# SCH_WEARBLE_HEALTH_MONITER_2024-07-04.net
KiCad netlist of a schematic drawn in EasyEDA
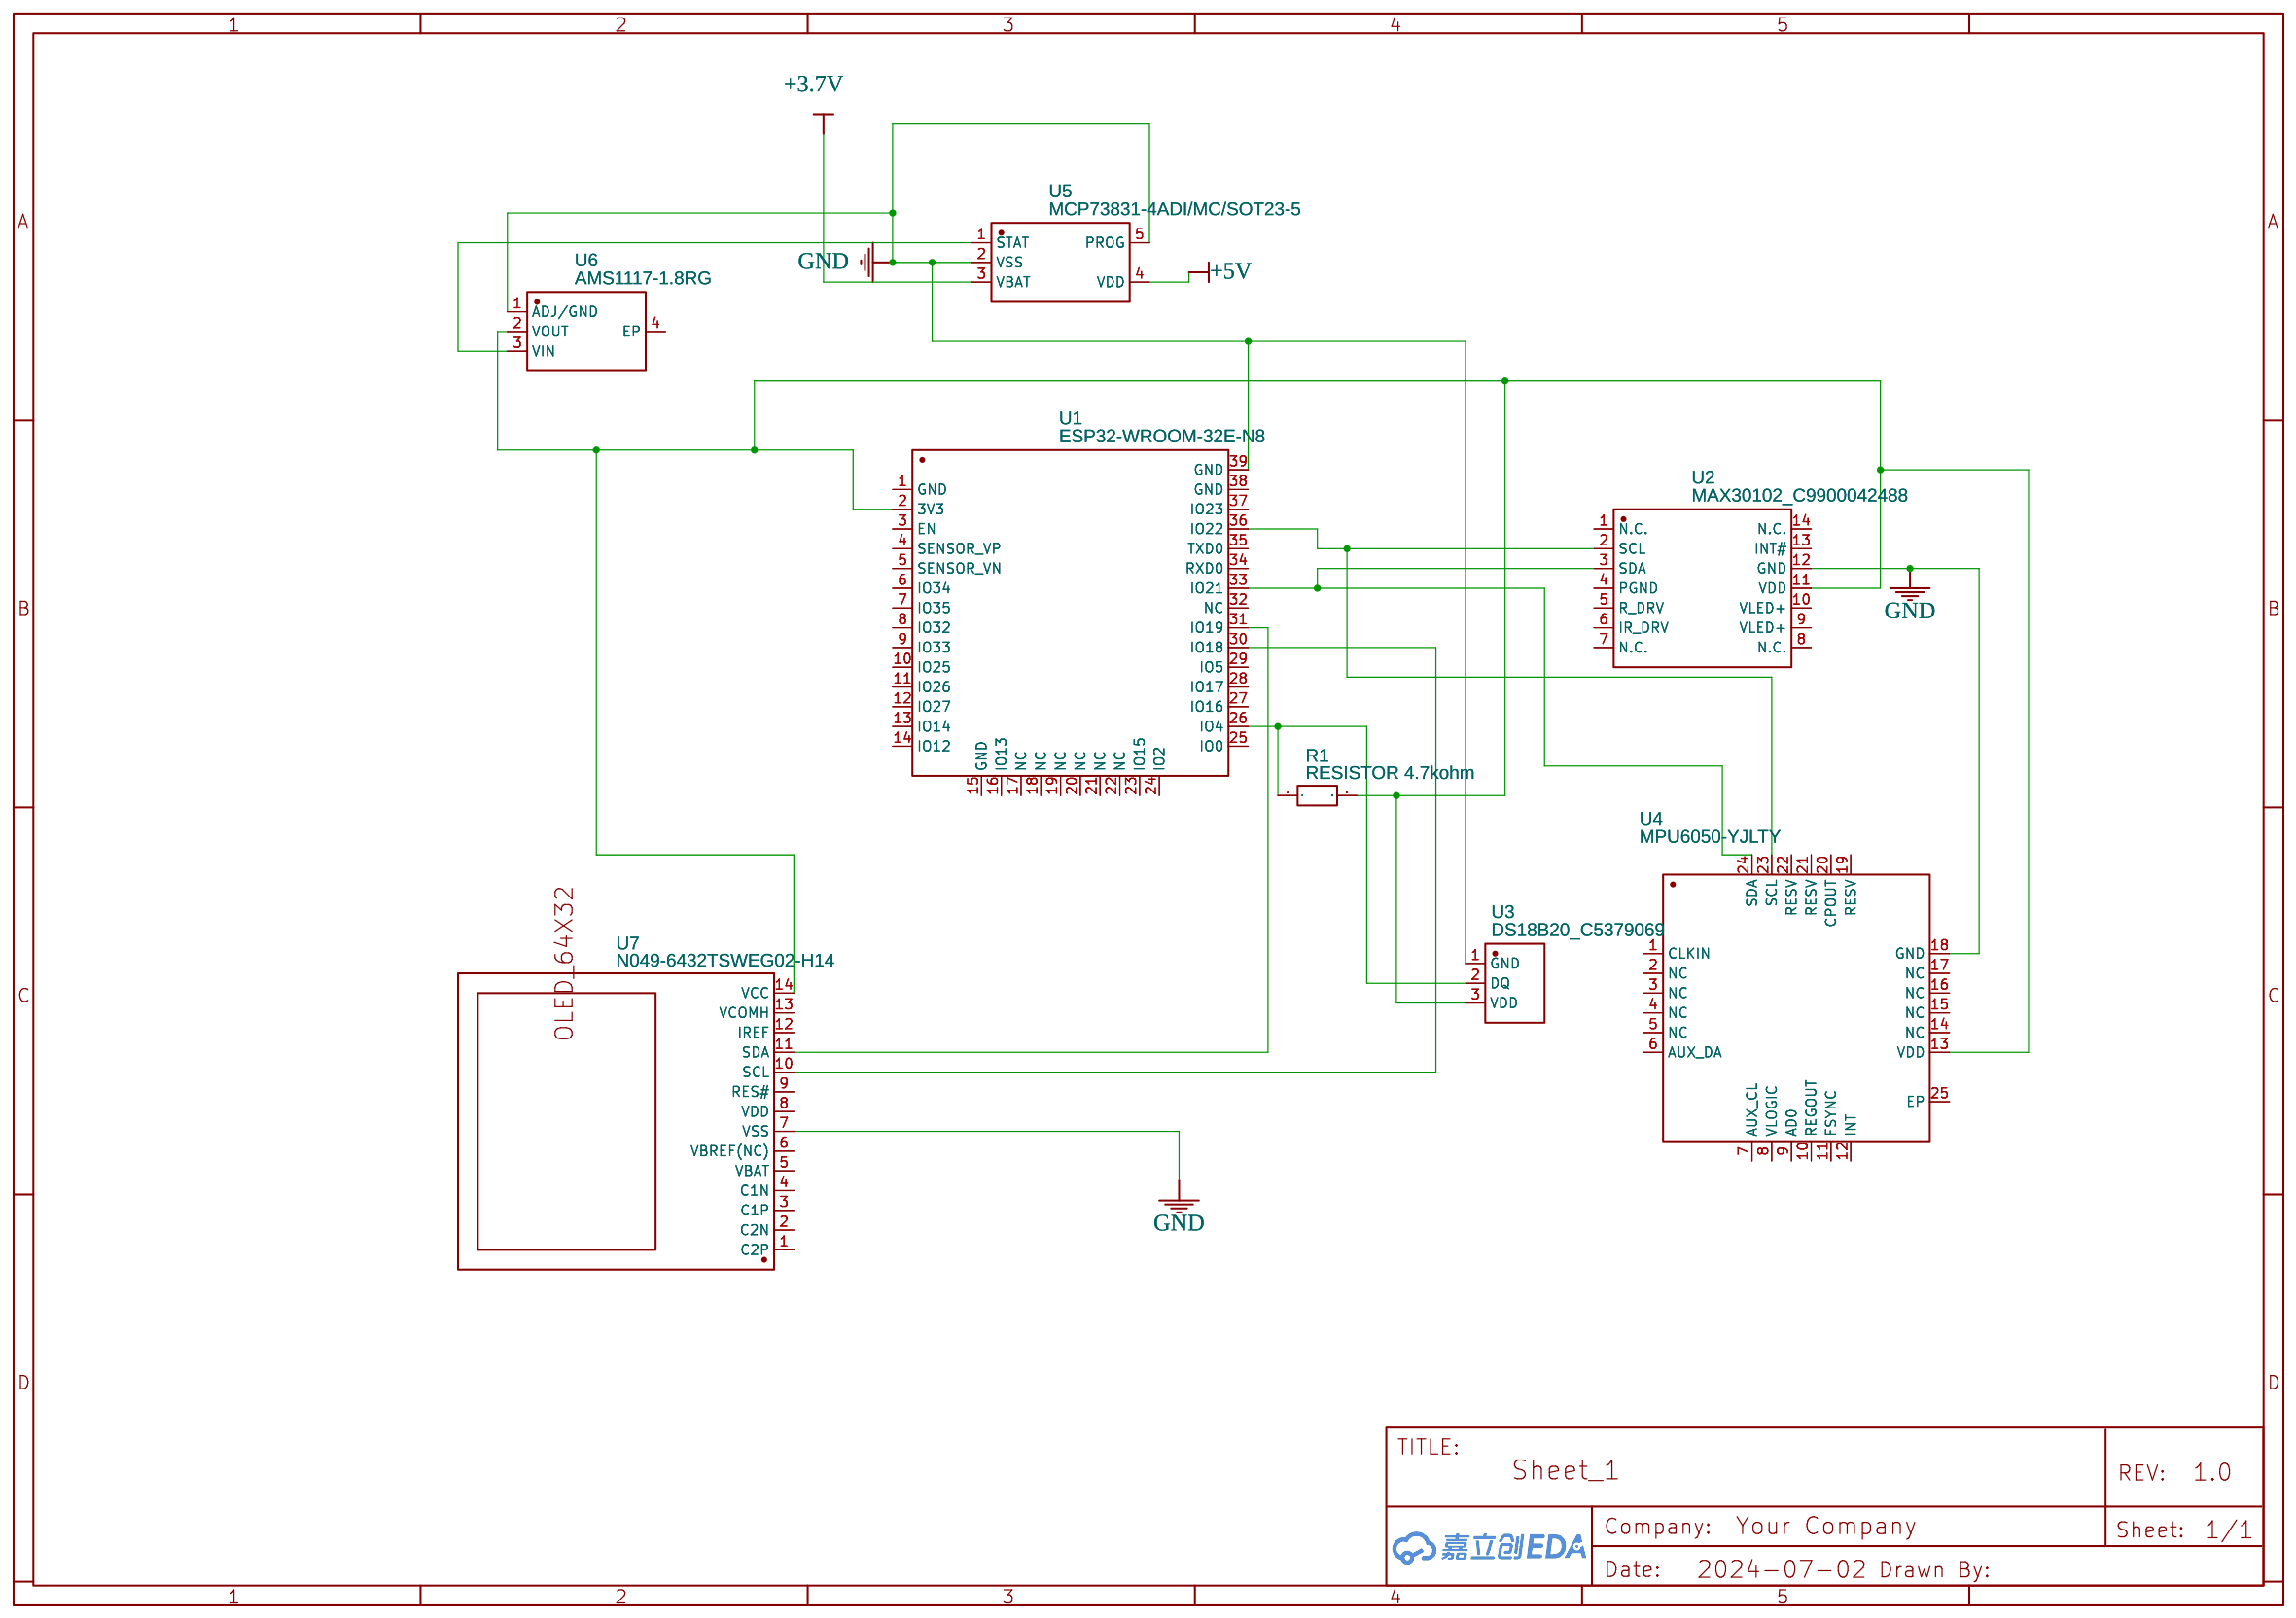
[diagram p0: schematic sheet]

(export (version "E")
  (design (tool "Eeschema 10.0.6"))
  (components
    (comp (ref "R1")
      (value "RESISTOR 4.7kohm")
      (fields
        (field (name "Manufacturer Part") "Resistor_THT:R_Axial_DIN0309_L9.0mm_D3.2mm_P2.54mm_Vertical")
      )
      (libsource (lib "") (part "RESISTOR_THT{colon}R_AXIAL_DIN0309_L9.0MM_D3.2MM_P2.54MM_VERTICAL"))
    )
    (comp (ref "U1")
      (value "ESP32-WROOM-32E-N8")
      (fields (field (name "Manufacturer Part") "ESP32-WROOM-32E-N8-被合并"))
      (libsource (lib "") (part "ESP32-WROOM-32E-N8"))
    )
    (comp (ref "U2")
      (value "MAX30102_C9900042488")
      (fields (field (name "Manufacturer Part") "MAX30102"))
      (libsource (lib "") (part "MAX30102_C9900042488"))
    )
    (comp (ref "U3")
      (value "DS18B20_C5379069")
      (fields (field (name "Manufacturer Part") "DS18B20") (field (name "Manufacturer") "MSKSEMI(美森科)"))
      (libsource (lib "") (part "DS18B20_C5379069"))
    )
    (comp (ref "U4") (value "MPU6050-YJLTY") (libsource (lib "") (part "MPU6050-YJLTY")))
    (comp (ref "U5")
      (value "MCP73831-4ADI/MC/SOT23-5")
      (libsource (lib "") (part "MCP73831-4ADI/MC/SOT23-5"))
    )
    (comp (ref "U6")
      (value "AMS1117-1.8RG")
      (fields (field (name "Manufacturer") "HGC(深圳汉芯)"))
      (libsource (lib "") (part "AMS1117-1.8RG"))
    )
    (comp (ref "U7")
      (value "N049-6432TSWEG02-H14")
      (fields (field (name "Manufacturer") "Newvision(新智景)"))
      (libsource (lib "") (part "N049-6432TSWEG02-H14"))
    )
  )
  (nets
    (net (code "1") (name "+3.7V") (class "Default")
      (node (ref "U5") (pin "3") (pinfunction "VBAT_3") (pintype "unspecified"))
    )
    (net (code "2") (name "+5V") (class "Default")
      (node (ref "U5") (pin "4") (pinfunction "VDD_4") (pintype "unspecified"))
    )
    (net (code "3") (name "GND") (class "Default")
      (node (ref "U1") (pin "39") (pinfunction "GND_39") (pintype "unspecified"))
      (node (ref "U2") (pin "12") (pinfunction "GND_12") (pintype "unspecified"))
      (node (ref "U3") (pin "1") (pinfunction "GND_1") (pintype "unspecified"))
      (node (ref "U4") (pin "18") (pinfunction "GND_18") (pintype "unspecified"))
      (node (ref "U5") (pin "2") (pinfunction "VSS_2") (pintype "unspecified"))
      (node (ref "U5") (pin "5") (pinfunction "PROG_5") (pintype "unspecified"))
      (node (ref "U6") (pin "1") (pinfunction "ADJ/GND_1") (pintype "unspecified"))
      (node (ref "U7") (pin "7") (pinfunction "VSS_7") (pintype "unspecified"))
    )
    (net (code "4") (name "Net-(U1-3V3)") (class "Default")
      (node (ref "R1") (pin "2") (pinfunction "2_2") (pintype "unspecified"))
      (node (ref "U1") (pin "2") (pinfunction "3V3_2") (pintype "unspecified"))
      (node (ref "U2") (pin "11") (pinfunction "VDD_11") (pintype "unspecified"))
      (node (ref "U3") (pin "3") (pinfunction "VDD_3") (pintype "unspecified"))
      (node (ref "U4") (pin "13") (pinfunction "VDD_13") (pintype "unspecified"))
      (node (ref "U6") (pin "2") (pinfunction "VOUT_2") (pintype "unspecified"))
      (node (ref "U7") (pin "14") (pinfunction "VCC_14") (pintype "unspecified"))
    )
    (net (code "5") (name "Net-(U1-IO4)") (class "Default")
      (node (ref "R1") (pin "1") (pinfunction "1_1") (pintype "unspecified"))
      (node (ref "U1") (pin "26") (pinfunction "IO4_26") (pintype "unspecified"))
      (node (ref "U3") (pin "2") (pinfunction "DQ_2") (pintype "unspecified"))
    )
    (net (code "6") (name "Net-(U1-IO18)") (class "Default")
      (node (ref "U1") (pin "30") (pinfunction "IO18_30") (pintype "unspecified"))
      (node (ref "U7") (pin "10") (pinfunction "SCL_10") (pintype "unspecified"))
    )
    (net (code "7") (name "Net-(U1-IO19)") (class "Default")
      (node (ref "U1") (pin "31") (pinfunction "IO19_31") (pintype "unspecified"))
      (node (ref "U7") (pin "11") (pinfunction "SDA_11") (pintype "unspecified"))
    )
    (net (code "8") (name "Net-(U1-IO21)") (class "Default")
      (node (ref "U1") (pin "33") (pinfunction "IO21_33") (pintype "unspecified"))
      (node (ref "U2") (pin "3") (pinfunction "SDA_3") (pintype "unspecified"))
      (node (ref "U4") (pin "24") (pinfunction "SDA_24") (pintype "unspecified"))
    )
    (net (code "9") (name "Net-(U1-IO22)") (class "Default")
      (node (ref "U1") (pin "36") (pinfunction "IO22_36") (pintype "unspecified"))
      (node (ref "U2") (pin "2") (pinfunction "SCL_2") (pintype "unspecified"))
      (node (ref "U4") (pin "23") (pinfunction "SCL_23") (pintype "unspecified"))
    )
    (net (code "10") (name "Net-(U5-STAT)") (class "Default")
      (node (ref "U5") (pin "1") (pinfunction "STAT_1") (pintype "unspecified"))
      (node (ref "U6") (pin "3") (pinfunction "VIN_3") (pintype "unspecified"))
    )
    (net (code "11") (name "unconnected-(U1-EN-Pad3)") (class "Default")
      (node (ref "U1") (pin "3") (pinfunction "EN_3") (pintype "unspecified"))
    )
    (net (code "12") (name "unconnected-(U1-GND-Pad1)") (class "Default")
      (node (ref "U1") (pin "1") (pinfunction "GND_1") (pintype "unspecified"))
    )
    (net (code "13") (name "unconnected-(U1-GND-Pad15)") (class "Default")
      (node (ref "U1") (pin "15") (pinfunction "GND_15") (pintype "unspecified"))
    )
    (net (code "14") (name "unconnected-(U1-GND-Pad38)") (class "Default")
      (node (ref "U1") (pin "38") (pinfunction "GND_38") (pintype "unspecified"))
    )
    (net (code "15") (name "unconnected-(U1-IO0-Pad25)") (class "Default")
      (node (ref "U1") (pin "25") (pinfunction "IO0_25") (pintype "unspecified"))
    )
    (net (code "16") (name "unconnected-(U1-IO2-Pad24)") (class "Default")
      (node (ref "U1") (pin "24") (pinfunction "IO2_24") (pintype "unspecified"))
    )
    (net (code "17") (name "unconnected-(U1-IO5-Pad29)") (class "Default")
      (node (ref "U1") (pin "29") (pinfunction "IO5_29") (pintype "unspecified"))
    )
    (net (code "18") (name "unconnected-(U1-IO12-Pad14)") (class "Default")
      (node (ref "U1") (pin "14") (pinfunction "IO12_14") (pintype "unspecified"))
    )
    (net (code "19") (name "unconnected-(U1-IO13-Pad16)") (class "Default")
      (node (ref "U1") (pin "16") (pinfunction "IO13_16") (pintype "unspecified"))
    )
    (net (code "20") (name "unconnected-(U1-IO14-Pad13)") (class "Default")
      (node (ref "U1") (pin "13") (pinfunction "IO14_13") (pintype "unspecified"))
    )
    (net (code "21") (name "unconnected-(U1-IO15-Pad23)") (class "Default")
      (node (ref "U1") (pin "23") (pinfunction "IO15_23") (pintype "unspecified"))
    )
    (net (code "22") (name "unconnected-(U1-IO16-Pad27)") (class "Default")
      (node (ref "U1") (pin "27") (pinfunction "IO16_27") (pintype "unspecified"))
    )
    (net (code "23") (name "unconnected-(U1-IO17-Pad28)") (class "Default")
      (node (ref "U1") (pin "28") (pinfunction "IO17_28") (pintype "unspecified"))
    )
    (net (code "24") (name "unconnected-(U1-IO23-Pad37)") (class "Default")
      (node (ref "U1") (pin "37") (pinfunction "IO23_37") (pintype "unspecified"))
    )
    (net (code "25") (name "unconnected-(U1-IO25-Pad10)") (class "Default")
      (node (ref "U1") (pin "10") (pinfunction "IO25_10") (pintype "unspecified"))
    )
    (net (code "26") (name "unconnected-(U1-IO26-Pad11)") (class "Default")
      (node (ref "U1") (pin "11") (pinfunction "IO26_11") (pintype "unspecified"))
    )
    (net (code "27") (name "unconnected-(U1-IO27-Pad12)") (class "Default")
      (node (ref "U1") (pin "12") (pinfunction "IO27_12") (pintype "unspecified"))
    )
    (net (code "28") (name "unconnected-(U1-IO32-Pad8)") (class "Default")
      (node (ref "U1") (pin "8") (pinfunction "IO32_8") (pintype "unspecified"))
    )
    (net (code "29") (name "unconnected-(U1-IO33-Pad9)") (class "Default")
      (node (ref "U1") (pin "9") (pinfunction "IO33_9") (pintype "unspecified"))
    )
    (net (code "30") (name "unconnected-(U1-IO34-Pad6)") (class "Default")
      (node (ref "U1") (pin "6") (pinfunction "IO34_6") (pintype "unspecified"))
    )
    (net (code "31") (name "unconnected-(U1-IO35-Pad7)") (class "Default")
      (node (ref "U1") (pin "7") (pinfunction "IO35_7") (pintype "unspecified"))
    )
    (net (code "32") (name "unconnected-(U1-NC-Pad17)") (class "Default")
      (node (ref "U1") (pin "17") (pinfunction "NC_17") (pintype "unspecified"))
    )
    (net (code "33") (name "unconnected-(U1-NC-Pad18)") (class "Default")
      (node (ref "U1") (pin "18") (pinfunction "NC_18") (pintype "unspecified"))
    )
    (net (code "34") (name "unconnected-(U1-NC-Pad19)") (class "Default")
      (node (ref "U1") (pin "19") (pinfunction "NC_19") (pintype "unspecified"))
    )
    (net (code "35") (name "unconnected-(U1-NC-Pad20)") (class "Default")
      (node (ref "U1") (pin "20") (pinfunction "NC_20") (pintype "unspecified"))
    )
    (net (code "36") (name "unconnected-(U1-NC-Pad21)") (class "Default")
      (node (ref "U1") (pin "21") (pinfunction "NC_21") (pintype "unspecified"))
    )
    (net (code "37") (name "unconnected-(U1-NC-Pad22)") (class "Default")
      (node (ref "U1") (pin "22") (pinfunction "NC_22") (pintype "unspecified"))
    )
    (net (code "38") (name "unconnected-(U1-NC-Pad32)") (class "Default")
      (node (ref "U1") (pin "32") (pinfunction "NC_32") (pintype "unspecified"))
    )
    (net (code "39") (name "unconnected-(U1-RXD0-Pad34)") (class "Default")
      (node (ref "U1") (pin "34") (pinfunction "RXD0_34") (pintype "unspecified"))
    )
    (net (code "40") (name "unconnected-(U1-SENSOR_VN-Pad5)") (class "Default")
      (node (ref "U1") (pin "5") (pinfunction "SENSOR_VN_5") (pintype "unspecified"))
    )
    (net (code "41") (name "unconnected-(U1-SENSOR_VP-Pad4)") (class "Default")
      (node (ref "U1") (pin "4") (pinfunction "SENSOR_VP_4") (pintype "unspecified"))
    )
    (net (code "42") (name "unconnected-(U1-TXD0-Pad35)") (class "Default")
      (node (ref "U1") (pin "35") (pinfunction "TXD0_35") (pintype "unspecified"))
    )
    (net (code "43") (name "unconnected-(U2-INT#-Pad13)") (class "Default")
      (node (ref "U2") (pin "13") (pinfunction "INT#_13") (pintype "unspecified"))
    )
    (net (code "44") (name "unconnected-(U2-IR_DRV-Pad6)") (class "Default")
      (node (ref "U2") (pin "6") (pinfunction "IR_DRV_6") (pintype "unspecified"))
    )
    (net (code "45") (name "unconnected-(U2-N.C.-Pad1)") (class "Default")
      (node (ref "U2") (pin "1") (pinfunction "N.C._1") (pintype "unspecified"))
    )
    (net (code "46") (name "unconnected-(U2-N.C.-Pad7)") (class "Default")
      (node (ref "U2") (pin "7") (pinfunction "N.C._7") (pintype "unspecified"))
    )
    (net (code "47") (name "unconnected-(U2-N.C.-Pad8)") (class "Default")
      (node (ref "U2") (pin "8") (pinfunction "N.C._8") (pintype "unspecified"))
    )
    (net (code "48") (name "unconnected-(U2-N.C.-Pad14)") (class "Default")
      (node (ref "U2") (pin "14") (pinfunction "N.C._14") (pintype "unspecified"))
    )
    (net (code "49") (name "unconnected-(U2-PGND-Pad4)") (class "Default")
      (node (ref "U2") (pin "4") (pinfunction "PGND_4") (pintype "unspecified"))
    )
    (net (code "50") (name "unconnected-(U2-R_DRV-Pad5)") (class "Default")
      (node (ref "U2") (pin "5") (pinfunction "R_DRV_5") (pintype "unspecified"))
    )
    (net (code "51") (name "unconnected-(U2-VLED+-Pad9)") (class "Default")
      (node (ref "U2") (pin "9") (pinfunction "VLED+_9") (pintype "unspecified"))
    )
    (net (code "52") (name "unconnected-(U2-VLED+-Pad10)") (class "Default")
      (node (ref "U2") (pin "10") (pinfunction "VLED+_10") (pintype "unspecified"))
    )
    (net (code "53") (name "unconnected-(U4-AD0-Pad9)") (class "Default")
      (node (ref "U4") (pin "9") (pinfunction "AD0_9") (pintype "unspecified"))
    )
    (net (code "54") (name "unconnected-(U4-AUX_CL-Pad7)") (class "Default")
      (node (ref "U4") (pin "7") (pinfunction "AUX_CL_7") (pintype "unspecified"))
    )
    (net (code "55") (name "unconnected-(U4-AUX_DA-Pad6)") (class "Default")
      (node (ref "U4") (pin "6") (pinfunction "AUX_DA_6") (pintype "unspecified"))
    )
    (net (code "56") (name "unconnected-(U4-CLKIN-Pad1)") (class "Default")
      (node (ref "U4") (pin "1") (pinfunction "CLKIN_1") (pintype "unspecified"))
    )
    (net (code "57") (name "unconnected-(U4-CPOUT-Pad20)") (class "Default")
      (node (ref "U4") (pin "20") (pinfunction "CPOUT_20") (pintype "unspecified"))
    )
    (net (code "58") (name "unconnected-(U4-EP-Pad25)") (class "Default")
      (node (ref "U4") (pin "25") (pinfunction "EP_25") (pintype "unspecified"))
    )
    (net (code "59") (name "unconnected-(U4-FSYNC-Pad11)") (class "Default")
      (node (ref "U4") (pin "11") (pinfunction "FSYNC_11") (pintype "unspecified"))
    )
    (net (code "60") (name "unconnected-(U4-INT-Pad12)") (class "Default")
      (node (ref "U4") (pin "12") (pinfunction "INT_12") (pintype "unspecified"))
    )
    (net (code "61") (name "unconnected-(U4-NC-Pad2)") (class "Default")
      (node (ref "U4") (pin "2") (pinfunction "NC_2") (pintype "unspecified"))
    )
    (net (code "62") (name "unconnected-(U4-NC-Pad3)") (class "Default")
      (node (ref "U4") (pin "3") (pinfunction "NC_3") (pintype "unspecified"))
    )
    (net (code "63") (name "unconnected-(U4-NC-Pad4)") (class "Default")
      (node (ref "U4") (pin "4") (pinfunction "NC_4") (pintype "unspecified"))
    )
    (net (code "64") (name "unconnected-(U4-NC-Pad5)") (class "Default")
      (node (ref "U4") (pin "5") (pinfunction "NC_5") (pintype "unspecified"))
    )
    (net (code "65") (name "unconnected-(U4-NC-Pad14)") (class "Default")
      (node (ref "U4") (pin "14") (pinfunction "NC_14") (pintype "unspecified"))
    )
    (net (code "66") (name "unconnected-(U4-NC-Pad15)") (class "Default")
      (node (ref "U4") (pin "15") (pinfunction "NC_15") (pintype "unspecified"))
    )
    (net (code "67") (name "unconnected-(U4-NC-Pad16)") (class "Default")
      (node (ref "U4") (pin "16") (pinfunction "NC_16") (pintype "unspecified"))
    )
    (net (code "68") (name "unconnected-(U4-NC-Pad17)") (class "Default")
      (node (ref "U4") (pin "17") (pinfunction "NC_17") (pintype "unspecified"))
    )
    (net (code "69") (name "unconnected-(U4-REGOUT-Pad10)") (class "Default")
      (node (ref "U4") (pin "10") (pinfunction "REGOUT_10") (pintype "unspecified"))
    )
    (net (code "70") (name "unconnected-(U4-RESV-Pad19)") (class "Default")
      (node (ref "U4") (pin "19") (pinfunction "RESV_19") (pintype "unspecified"))
    )
    (net (code "71") (name "unconnected-(U4-RESV-Pad21)") (class "Default")
      (node (ref "U4") (pin "21") (pinfunction "RESV_21") (pintype "unspecified"))
    )
    (net (code "72") (name "unconnected-(U4-RESV-Pad22)") (class "Default")
      (node (ref "U4") (pin "22") (pinfunction "RESV_22") (pintype "unspecified"))
    )
    (net (code "73") (name "unconnected-(U4-VLOGIC-Pad8)") (class "Default")
      (node (ref "U4") (pin "8") (pinfunction "VLOGIC_8") (pintype "unspecified"))
    )
    (net (code "74") (name "unconnected-(U6-EP-Pad4)") (class "Default")
      (node (ref "U6") (pin "4") (pinfunction "EP_4") (pintype "unspecified"))
    )
    (net (code "75") (name "unconnected-(U7-C1N-Pad4)") (class "Default")
      (node (ref "U7") (pin "4") (pinfunction "C1N_4") (pintype "unspecified"))
    )
    (net (code "76") (name "unconnected-(U7-C1P-Pad3)") (class "Default")
      (node (ref "U7") (pin "3") (pinfunction "C1P_3") (pintype "unspecified"))
    )
    (net (code "77") (name "unconnected-(U7-C2N-Pad2)") (class "Default")
      (node (ref "U7") (pin "2") (pinfunction "C2N_2") (pintype "unspecified"))
    )
    (net (code "78") (name "unconnected-(U7-C2P-Pad1)") (class "Default")
      (node (ref "U7") (pin "1") (pinfunction "C2P_1") (pintype "unspecified"))
    )
    (net (code "79") (name "unconnected-(U7-IREF-Pad12)") (class "Default")
      (node (ref "U7") (pin "12") (pinfunction "IREF_12") (pintype "unspecified"))
    )
    (net (code "80") (name "unconnected-(U7-RES#-Pad9)") (class "Default")
      (node (ref "U7") (pin "9") (pinfunction "RES#_9") (pintype "unspecified"))
    )
    (net (code "81") (name "unconnected-(U7-VBAT-Pad5)") (class "Default")
      (node (ref "U7") (pin "5") (pinfunction "VBAT_5") (pintype "unspecified"))
    )
    (net (code "82") (name "unconnected-(U7-VBREF(NC)-Pad6)") (class "Default")
      (node (ref "U7") (pin "6") (pinfunction "VBREF(NC)_6") (pintype "unspecified"))
    )
    (net (code "83") (name "unconnected-(U7-VCOMH-Pad13)") (class "Default")
      (node (ref "U7") (pin "13") (pinfunction "VCOMH_13") (pintype "unspecified"))
    )
    (net (code "84") (name "unconnected-(U7-VDD-Pad8)") (class "Default")
      (node (ref "U7") (pin "8") (pinfunction "VDD_8") (pintype "unspecified"))
    )
  )
)
